# Bluetooth.net
KiCad netlist of a schematic drawn in Altium Designer
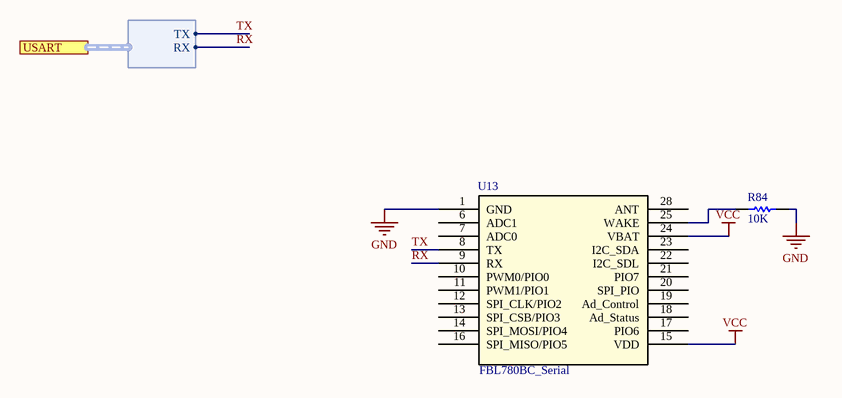
[diagram p0: Bluetooth.SchDoc]

(export (version "E")
  (design (tool "Eeschema 10.0.6"))
  (components
    (comp (ref "R84")
      (value "10K")
      (footprint "R0603[1608]")
      (description "10K 0.25W 1% 0603 (1005 Metric)")
      (fields (field (name "MANUFACTURER") "Vishay") (field (name "PARTNUMBER") "RCS060310K0FKEA"))
      (libsource (lib "Resistors") (part "RES_10K_0603_1%"))
    )
    (comp (ref "U13")
      (value "FBL780BC_Serial")
      (footprint "General_Footprint:FBL780BC_Serial")
      (fields (field (name "MANUFACTURER") "Firmtech"))
      (libsource (lib "General_Component") (part "FBL780BC_Serial"))
    )
  )
  (nets
    (net (code "2") (name "/RX") (class "Default")
      (node (ref "U13") (pin "9") (pinfunction "RX_9") (pintype "passive"))
    )
    (net (code "3") (name "/TX") (class "Default")
      (node (ref "U13") (pin "8") (pinfunction "TX_8") (pintype "passive"))
    )
    (net (code "5") (name "GND") (class "Default")
      (node (ref "R84") (pin "2") (pinfunction "2_2") (pintype "passive"))
      (node (ref "U13") (pin "1") (pinfunction "GND_1") (pintype "power_in"))
    )
    (net (code "6") (name "Net-(U13-WAKE)") (class "Default")
      (node (ref "R84") (pin "1") (pinfunction "1_1") (pintype "passive"))
      (node (ref "U13") (pin "25") (pinfunction "WAKE_25") (pintype "passive"))
    )
    (net (code "7") (name "VCC") (class "Default")
      (node (ref "U13") (pin "15") (pinfunction "VDD_15") (pintype "power_in"))
      (node (ref "U13") (pin "24") (pinfunction "VBAT_24") (pintype "power_in"))
    )
    (net (code "8") (name "unconnected-(U13-ADC0-Pad7)") (class "Default")
      (node (ref "U13") (pin "7") (pinfunction "ADC0_7") (pintype "passive"))
    )
    (net (code "9") (name "unconnected-(U13-ADC1-Pad6)") (class "Default")
      (node (ref "U13") (pin "6") (pinfunction "ADC1_6") (pintype "passive"))
    )
    (net (code "10") (name "unconnected-(U13-ANT-Pad28)") (class "Default")
      (node (ref "U13") (pin "28") (pinfunction "ANT_28") (pintype "passive"))
    )
    (net (code "11") (name "unconnected-(U13-Ad_Control-Pad19)") (class "Default")
      (node (ref "U13") (pin "19") (pinfunction "Ad_Control_19") (pintype "passive"))
    )
    (net (code "12") (name "unconnected-(U13-Ad_Status-Pad18)") (class "Default")
      (node (ref "U13") (pin "18") (pinfunction "Ad_Status_18") (pintype "passive"))
    )
    (net (code "13") (name "unconnected-(U13-I2C_SDA-Pad23)") (class "Default")
      (node (ref "U13") (pin "23") (pinfunction "I2C_SDA_23") (pintype "passive"))
    )
    (net (code "14") (name "unconnected-(U13-I2C_SDL-Pad22)") (class "Default")
      (node (ref "U13") (pin "22") (pinfunction "I2C_SDL_22") (pintype "passive"))
    )
    (net (code "15") (name "unconnected-(U13-PIO6-Pad17)") (class "Default")
      (node (ref "U13") (pin "17") (pinfunction "PIO6_17") (pintype "passive"))
    )
    (net (code "16") (name "unconnected-(U13-PIO7-Pad21)") (class "Default")
      (node (ref "U13") (pin "21") (pinfunction "PIO7_21") (pintype "passive"))
    )
    (net (code "17") (name "unconnected-(U13-PWM0{slash}PIO0-Pad10)") (class "Default")
      (node (ref "U13") (pin "10") (pinfunction "PWM0/PIO0_10") (pintype "passive"))
    )
    (net (code "18") (name "unconnected-(U13-PWM1{slash}PIO1-Pad11)") (class "Default")
      (node (ref "U13") (pin "11") (pinfunction "PWM1/PIO1_11") (pintype "passive"))
    )
    (net (code "19") (name "unconnected-(U13-SPI_CLK{slash}PIO2-Pad12)") (class "Default")
      (node (ref "U13") (pin "12") (pinfunction "SPI_CLK/PIO2_12") (pintype "passive"))
    )
    (net (code "20") (name "unconnected-(U13-SPI_CSB{slash}PIO3-Pad13)") (class "Default")
      (node (ref "U13") (pin "13") (pinfunction "SPI_CSB/PIO3_13") (pintype "passive"))
    )
    (net (code "21") (name "unconnected-(U13-SPI_MISO{slash}PIO5-Pad16)") (class "Default")
      (node (ref "U13") (pin "16") (pinfunction "SPI_MISO/PIO5_16") (pintype "passive"))
    )
    (net (code "22") (name "unconnected-(U13-SPI_MOSI{slash}PIO4-Pad14)") (class "Default")
      (node (ref "U13") (pin "14") (pinfunction "SPI_MOSI/PIO4_14") (pintype "passive"))
    )
    (net (code "23") (name "unconnected-(U13-SPI_PIO-Pad20)") (class "Default")
      (node (ref "U13") (pin "20") (pinfunction "SPI_PIO_20") (pintype "passive"))
    )
  )
)
